# 07-USB_HOST.net
KiCad netlist of a schematic drawn in Altium Designer
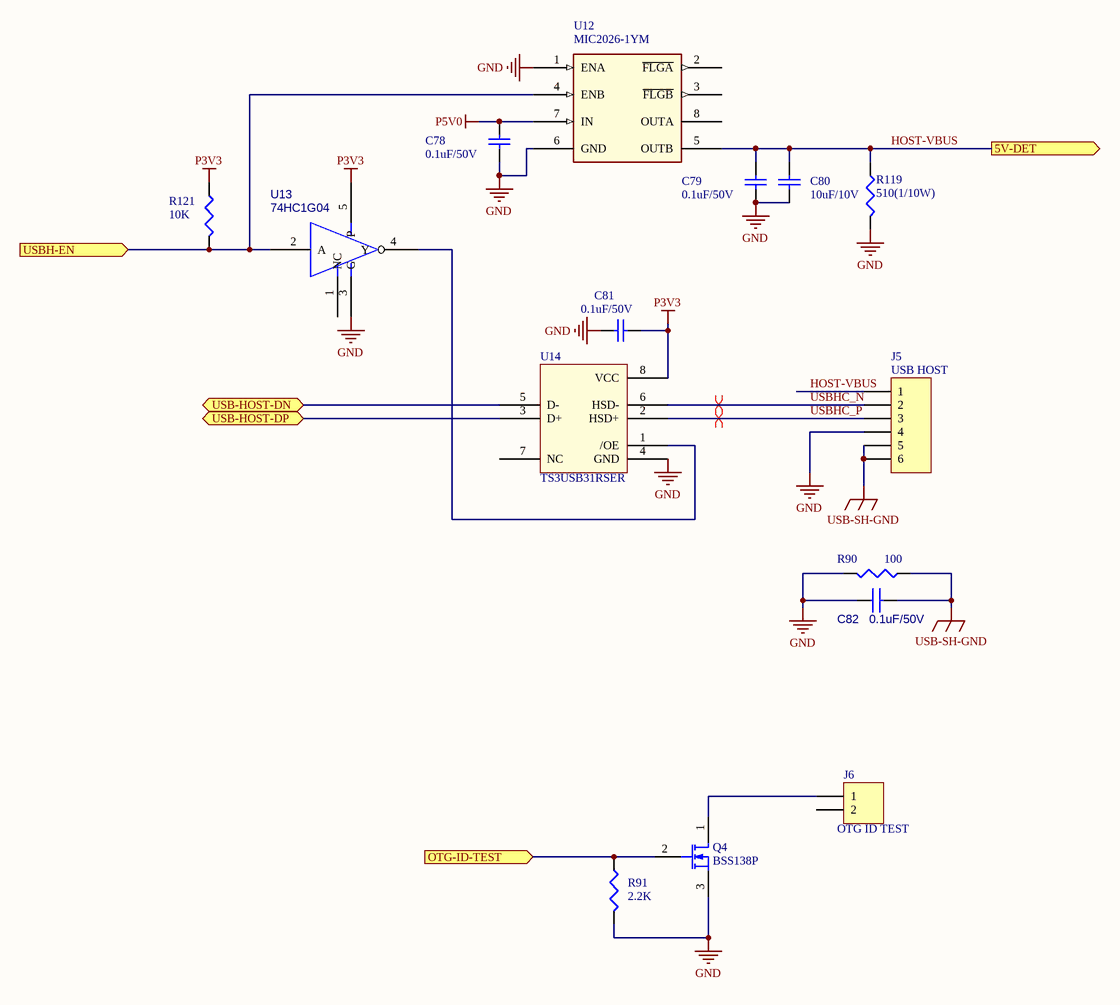
[diagram p0: 07-USB_HOST.SchDoc]

(export (version "E")
  (design (tool "Eeschema 10.0.6"))
  (components
    (comp (ref "C78")
      (value "0.1uF/50V")
      (footprint "0402")
      (description "Capacitor")
      (fields (field (name "PUBLISHER") "Altium Limited"))
      (libsource (lib "Miscellaneous Devices") (part "Cap"))
    )
    (comp (ref "C79")
      (value "0.1uF/50V")
      (footprint "0402")
      (description "Capacitor")
      (fields (field (name "PUBLISHER") "Altium Limited"))
      (libsource (lib "Miscellaneous Devices") (part "Cap"))
    )
    (comp (ref "C80")
      (value "10uF/10V")
      (footprint "0805")
      (description "Capacitor")
      (fields (field (name "PUBLISHER") "Altium Limited"))
      (libsource (lib "Miscellaneous Devices") (part "Cap"))
    )
    (comp (ref "C81")
      (value "0.1uF/50V")
      (footprint "0402")
      (description "Capacitor")
      (fields (field (name "PUBLISHER") "Altium Limited"))
      (libsource (lib "Miscellaneous Devices") (part "Cap"))
    )
    (comp (ref "C82") (value "0.1uF/50V") (libsource (lib "*") (part "CAP_Dup1")))
    (comp (ref "J5")
      (value "USB HOST")
      (footprint "USB-HOST")
      (description "Header, 6-Pin")
      (libsource (lib "Miscellaneous Connectors") (part "Header 6"))
    )
    (comp (ref "J6")
      (value "OTG ID TEST")
      (footprint "3030WR-S-2*1P")
      (description "Header, 2-Pin")
      (fields (field (name "PUBLISHER") "Altium Limited"))
      (libsource (lib "Miscellaneous Connectors") (part "Header 2"))
    )
    (comp (ref "Q4")
      (value "BSS138P")
      (footprint "NPN")
      (description "N-Channel MOSFET")
      (fields (field (name "PUBLISHER") "Altium Limited"))
      (libsource (lib "Miscellaneous Devices") (part "MOSFET-N"))
    )
    (comp (ref "R90") (value "100") (footprint "0402") (libsource (lib "*") (part "CR16-1003FM")))
    (comp (ref "R91")
      (value "2.2K")
      (footprint "0402")
      (description "Resistor")
      (fields (field (name "PUBLISHER") "Altium Limited"))
      (libsource (lib "Miscellaneous Devices") (part "Res3"))
    )
    (comp (ref "R119") (value "510(1/10W)") (footprint "0805") (libsource (lib "*") (part "CR16-1003FM")))
    (comp (ref "R121") (value "10K") (footprint "0402") (libsource (lib "*") (part "CR16-1003FM")))
    (comp (ref "U12")
      (value "MIC2026-1YM")
      (footprint "SO8")
      (description "IC LIN SW PWR ACTIVE HIGH DUAL 2.7V-5.5V 0.5A SOIC8")
      (libsource (lib "*") (part "MIC2526_8P"))
    )
    (comp (ref "U13") (value "74HC1G04") (libsource (lib "*") (part "74LVC1G04GW_SOT353-5")))
    (comp (ref "U14")
      (value "TS3USB31RSER")
      (footprint "UQFN8")
      (libsource (lib "Schlib") (part "TS3USB31RSER"))
    )
  )
  (nets
    (net (code "1") (name "/HOST-VBUS") (class "Default")
      (node (ref "C79") (pin "1") (pinfunction "1_1") (pintype "passive"))
      (node (ref "C80") (pin "1") (pinfunction "1_1") (pintype "passive"))
      (node (ref "J5") (pin "1") (pinfunction "1_1") (pintype "passive"))
      (node (ref "R119") (pin "1") (pinfunction "1_1") (pintype "passive"))
      (node (ref "U12") (pin "5") (pinfunction "OUTB_5") (pintype "power_in"))
    )
    (net (code "2") (name "/OTG-ID-TEST") (class "Default")
      (node (ref "Q4") (pin "2") (pinfunction "G_2") (pintype "passive"))
      (node (ref "R91") (pin "1") (pinfunction "1_1") (pintype "passive"))
    )
    (net (code "3") (name "/USB-HOST-DN") (class "Default")
      (node (ref "U14") (pin "5") (pinfunction "D-_5") (pintype "passive"))
    )
    (net (code "4") (name "/USB-HOST-DP") (class "Default")
      (node (ref "U14") (pin "3") (pinfunction "D+_3") (pintype "passive"))
    )
    (net (code "5") (name "/USBH-EN") (class "Default")
      (node (ref "R121") (pin "2") (pinfunction "2_2") (pintype "passive"))
      (node (ref "U12") (pin "4") (pinfunction "ENB_4") (pintype "input"))
      (node (ref "U13") (pin "2") (pinfunction "A_2") (pintype "passive"))
    )
    (net (code "6") (name "/USBHC_N") (class "Default")
      (node (ref "J5") (pin "2") (pinfunction "2_2") (pintype "passive"))
      (node (ref "U14") (pin "6") (pinfunction "HSD-_6") (pintype "passive"))
    )
    (net (code "7") (name "/USBHC_P") (class "Default")
      (node (ref "J5") (pin "3") (pinfunction "3_3") (pintype "passive"))
      (node (ref "U14") (pin "2") (pinfunction "HSD+_2") (pintype "passive"))
    )
    (net (code "8") (name "GND") (class "Default")
      (node (ref "C78") (pin "2") (pinfunction "2_2") (pintype "passive"))
      (node (ref "C79") (pin "2") (pinfunction "2_2") (pintype "passive"))
      (node (ref "C80") (pin "2") (pinfunction "2_2") (pintype "passive"))
      (node (ref "C81") (pin "2") (pinfunction "2_2") (pintype "passive"))
      (node (ref "C82") (pin "1") (pinfunction "1_1") (pintype "passive"))
      (node (ref "J5") (pin "4") (pinfunction "4_4") (pintype "passive"))
      (node (ref "Q4") (pin "3") (pinfunction "S_3") (pintype "passive"))
      (node (ref "R119") (pin "2") (pinfunction "2_2") (pintype "passive"))
      (node (ref "R90") (pin "2") (pinfunction "2_2") (pintype "passive"))
      (node (ref "R91") (pin "2") (pinfunction "2_2") (pintype "passive"))
      (node (ref "U12") (pin "1") (pinfunction "ENA_1") (pintype "input"))
      (node (ref "U12") (pin "6") (pinfunction "GND_6") (pintype "power_in"))
      (node (ref "U13") (pin "3") (pinfunction "G_3") (pintype "passive"))
      (node (ref "U14") (pin "4") (pinfunction "GND_4") (pintype "passive"))
    )
    (net (code "9") (name "Net-(Q4-D)") (class "Default")
      (node (ref "J6") (pin "1") (pinfunction "1_1") (pintype "passive"))
      (node (ref "Q4") (pin "1") (pinfunction "D_1") (pintype "passive"))
    )
    (net (code "10") (name "Net-(U13-Y)") (class "Default")
      (node (ref "U13") (pin "4") (pinfunction "Y_4") (pintype "passive"))
      (node (ref "U14") (pin "1") (pinfunction "/OE_1") (pintype "passive"))
    )
    (net (code "11") (name "P3V3") (class "Default")
      (node (ref "C81") (pin "1") (pinfunction "1_1") (pintype "passive"))
      (node (ref "R121") (pin "1") (pinfunction "1_1") (pintype "passive"))
      (node (ref "U13") (pin "5") (pinfunction "P_5") (pintype "passive"))
      (node (ref "U14") (pin "8") (pinfunction "VCC_8") (pintype "passive"))
    )
    (net (code "12") (name "P5V0") (class "Default")
      (node (ref "C78") (pin "1") (pinfunction "1_1") (pintype "passive"))
      (node (ref "U12") (pin "7") (pinfunction "IN_7") (pintype "input"))
    )
    (net (code "13") (name "USB-SH-GND") (class "Default")
      (node (ref "C82") (pin "2") (pinfunction "2_2") (pintype "passive"))
      (node (ref "J5") (pin "5") (pinfunction "5_5") (pintype "passive"))
      (node (ref "J5") (pin "6") (pinfunction "6_6") (pintype "passive"))
      (node (ref "R90") (pin "1") (pinfunction "1_1") (pintype "passive"))
    )
    (net (code "14") (name "unconnected-(J6-Pad2)") (class "Default")
      (node (ref "J6") (pin "2") (pinfunction "2_2") (pintype "passive"))
    )
    (net (code "15") (name "unconnected-(U12-OUTA-Pad8)") (class "Default")
      (node (ref "U12") (pin "8") (pinfunction "OUTA_8") (pintype "power_in"))
    )
    (net (code "16") (name "unconnected-(U12-~{FLGA}-Pad2)") (class "Default")
      (node (ref "U12") (pin "2") (pinfunction "~{FLGA}_2") (pintype "output"))
    )
    (net (code "17") (name "unconnected-(U12-~{FLGB}-Pad3)") (class "Default")
      (node (ref "U12") (pin "3") (pinfunction "~{FLGB}_3") (pintype "output"))
    )
    (net (code "18") (name "unconnected-(U13-NC-Pad1)") (class "Default")
      (node (ref "U13") (pin "1") (pinfunction "NC_1") (pintype "passive"))
    )
    (net (code "19") (name "unconnected-(U14-NC-Pad7)") (class "Default")
      (node (ref "U14") (pin "7") (pinfunction "NC_7") (pintype "passive"))
    )
  )
)
